# afron_line_sensor.net
KiCad netlist of a schematic drawn in EAGLE
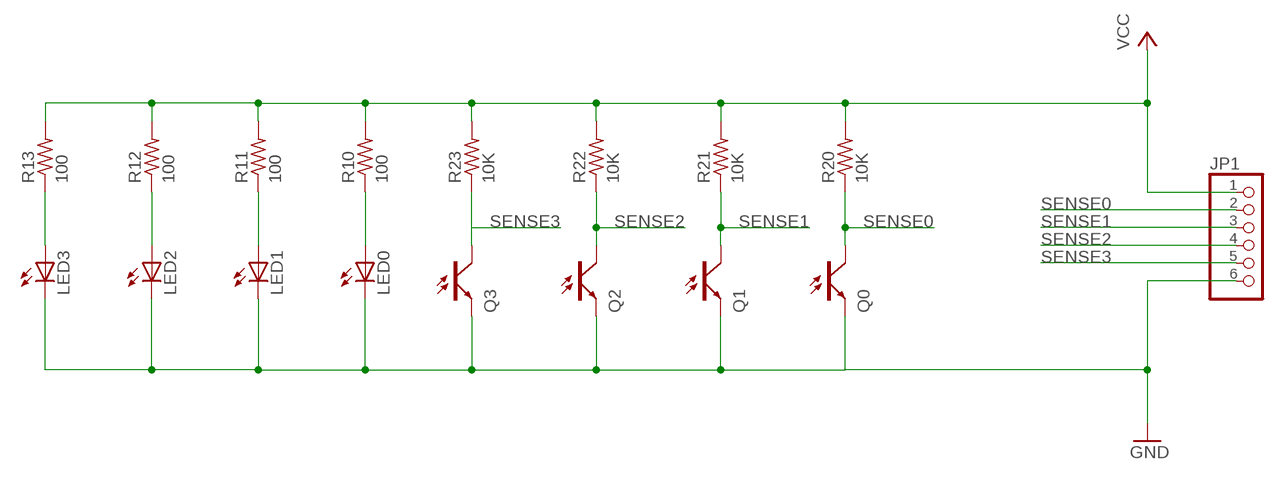
[diagram p0: schematic, sheet 1]

(export (version "E")
  (design (tool "Eeschema 10.0.6"))
  (components
    (comp (ref "JP1")
      (value "PINHD-1X06_2.54")
      (footprint "eagle-import:1X06")
      (libsource (lib "eagle-import") (part "PINHD-1X06_2.54"))
    )
    (comp (ref "LED0")
      (value "LED3MM")
      (footprint "eagle-import:LED3MM")
      (libsource (lib "eagle-import") (part "LED3MM"))
    )
    (comp (ref "LED1")
      (value "LED3MM")
      (footprint "eagle-import:LED3MM")
      (libsource (lib "eagle-import") (part "LED3MM"))
    )
    (comp (ref "LED2")
      (value "LED3MM")
      (footprint "eagle-import:LED3MM")
      (libsource (lib "eagle-import") (part "LED3MM"))
    )
    (comp (ref "LED3")
      (value "LED3MM")
      (footprint "eagle-import:LED3MM")
      (libsource (lib "eagle-import") (part "LED3MM"))
    )
    (comp (ref "Q0")
      (value "PHOTOTRANSISTOR3MM")
      (footprint "eagle-import:LED3MM")
      (libsource (lib "eagle-import") (part "PHOTOTRANSISTOR3MM"))
    )
    (comp (ref "Q1")
      (value "PHOTOTRANSISTOR3MM")
      (footprint "eagle-import:LED3MM")
      (libsource (lib "eagle-import") (part "PHOTOTRANSISTOR3MM"))
    )
    (comp (ref "Q2")
      (value "PHOTOTRANSISTOR3MM")
      (footprint "eagle-import:LED3MM")
      (libsource (lib "eagle-import") (part "PHOTOTRANSISTOR3MM"))
    )
    (comp (ref "Q3")
      (value "PHOTOTRANSISTOR3MM")
      (footprint "eagle-import:LED3MM")
      (libsource (lib "eagle-import") (part "PHOTOTRANSISTOR3MM"))
    )
    (comp (ref "R10")
      (value "100")
      (footprint "eagle-import:0204_5")
      (libsource (lib "eagle-import") (part "R-US_0204/5"))
    )
    (comp (ref "R11")
      (value "100")
      (footprint "eagle-import:0204_5")
      (libsource (lib "eagle-import") (part "R-US_0204/5"))
    )
    (comp (ref "R12")
      (value "100")
      (footprint "eagle-import:0204_5")
      (libsource (lib "eagle-import") (part "R-US_0204/5"))
    )
    (comp (ref "R13")
      (value "100")
      (footprint "eagle-import:0204_5")
      (libsource (lib "eagle-import") (part "R-US_0204/5"))
    )
    (comp (ref "R20")
      (value "10K")
      (footprint "eagle-import:0204_5")
      (libsource (lib "eagle-import") (part "R-US_0204/5"))
    )
    (comp (ref "R21")
      (value "10K")
      (footprint "eagle-import:0204_5")
      (libsource (lib "eagle-import") (part "R-US_0204/5"))
    )
    (comp (ref "R22")
      (value "10K")
      (footprint "eagle-import:0204_5")
      (libsource (lib "eagle-import") (part "R-US_0204/5"))
    )
    (comp (ref "R23")
      (value "10K")
      (footprint "eagle-import:0204_5")
      (libsource (lib "eagle-import") (part "R-US_0204/5"))
    )
  )
  (nets
    (net (code "1") (name "/SENSE0") (class "Default")
      (node (ref "JP1") (pin "2") (pinfunction "2_2") (pintype "passive"))
      (node (ref "Q0") (pin "A") (pinfunction "A_A") (pintype "passive"))
      (node (ref "R20") (pin "1") (pinfunction "1_1") (pintype "passive"))
    )
    (net (code "2") (name "/SENSE1") (class "Default")
      (node (ref "JP1") (pin "3") (pinfunction "3_3") (pintype "passive"))
      (node (ref "Q1") (pin "A") (pinfunction "A_A") (pintype "passive"))
      (node (ref "R21") (pin "1") (pinfunction "1_1") (pintype "passive"))
    )
    (net (code "3") (name "/SENSE2") (class "Default")
      (node (ref "JP1") (pin "4") (pinfunction "4_4") (pintype "passive"))
      (node (ref "Q2") (pin "A") (pinfunction "A_A") (pintype "passive"))
      (node (ref "R22") (pin "1") (pinfunction "1_1") (pintype "passive"))
    )
    (net (code "4") (name "/SENSE3") (class "Default")
      (node (ref "JP1") (pin "5") (pinfunction "5_5") (pintype "passive"))
      (node (ref "Q3") (pin "A") (pinfunction "A_A") (pintype "passive"))
      (node (ref "R23") (pin "1") (pinfunction "1_1") (pintype "passive"))
    )
    (net (code "5") (name "GND") (class "Default")
      (node (ref "JP1") (pin "6") (pinfunction "6_6") (pintype "passive"))
      (node (ref "LED0") (pin "K") (pinfunction "C_K") (pintype "passive"))
      (node (ref "LED1") (pin "K") (pinfunction "C_K") (pintype "passive"))
      (node (ref "LED2") (pin "K") (pinfunction "C_K") (pintype "passive"))
      (node (ref "LED3") (pin "K") (pinfunction "C_K") (pintype "passive"))
      (node (ref "Q0") (pin "K") (pinfunction "C_K") (pintype "passive"))
      (node (ref "Q1") (pin "K") (pinfunction "C_K") (pintype "passive"))
      (node (ref "Q2") (pin "K") (pinfunction "C_K") (pintype "passive"))
      (node (ref "Q3") (pin "K") (pinfunction "C_K") (pintype "passive"))
    )
    (net (code "6") (name "Net-(LED0-PadA)") (class "Default")
      (node (ref "LED0") (pin "A") (pinfunction "A_A") (pintype "passive"))
      (node (ref "R10") (pin "1") (pinfunction "1_1") (pintype "passive"))
    )
    (net (code "7") (name "Net-(LED1-PadA)") (class "Default")
      (node (ref "LED1") (pin "A") (pinfunction "A_A") (pintype "passive"))
      (node (ref "R11") (pin "1") (pinfunction "1_1") (pintype "passive"))
    )
    (net (code "8") (name "Net-(LED2-PadA)") (class "Default")
      (node (ref "LED2") (pin "A") (pinfunction "A_A") (pintype "passive"))
      (node (ref "R12") (pin "1") (pinfunction "1_1") (pintype "passive"))
    )
    (net (code "9") (name "Net-(LED3-PadA)") (class "Default")
      (node (ref "LED3") (pin "A") (pinfunction "A_A") (pintype "passive"))
      (node (ref "R13") (pin "1") (pinfunction "1_1") (pintype "passive"))
    )
    (net (code "10") (name "VCC") (class "Default")
      (node (ref "JP1") (pin "1") (pinfunction "1_1") (pintype "passive"))
      (node (ref "R10") (pin "2") (pinfunction "2_2") (pintype "passive"))
      (node (ref "R11") (pin "2") (pinfunction "2_2") (pintype "passive"))
      (node (ref "R12") (pin "2") (pinfunction "2_2") (pintype "passive"))
      (node (ref "R13") (pin "2") (pinfunction "2_2") (pintype "passive"))
      (node (ref "R20") (pin "2") (pinfunction "2_2") (pintype "passive"))
      (node (ref "R21") (pin "2") (pinfunction "2_2") (pintype "passive"))
      (node (ref "R22") (pin "2") (pinfunction "2_2") (pintype "passive"))
      (node (ref "R23") (pin "2") (pinfunction "2_2") (pintype "passive"))
    )
  )
)
